# irDA.net
KiCad netlist of a schematic drawn in EAGLE
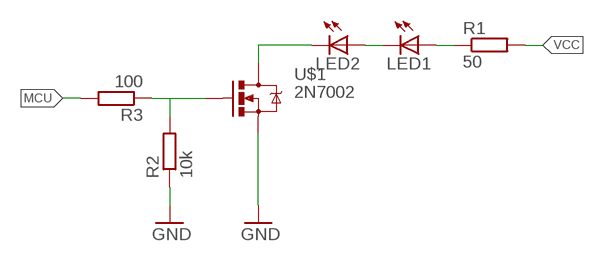
[diagram p0: schematic, sheet 1]

(export (version "E")
  (design (tool "Eeschema 10.0.6"))
  (components
    (comp (ref "LED1")
      (value "LED5MM")
      (footprint "eagle-import:LED5MM")
      (libsource (lib "eagle-import") (part "LED5MM"))
    )
    (comp (ref "LED2")
      (value "LED5MM")
      (footprint "eagle-import:LED5MM")
      (libsource (lib "eagle-import") (part "LED5MM"))
    )
    (comp (ref "R1")
      (value "50")
      (footprint "eagle-import:R0805")
      (libsource (lib "eagle-import") (part "R0805"))
    )
    (comp (ref "R2")
      (value "10k")
      (footprint "eagle-import:0603")
      (libsource (lib "eagle-import") (part "R0603"))
    )
    (comp (ref "R3")
      (value "100")
      (footprint "eagle-import:0603")
      (libsource (lib "eagle-import") (part "R0603"))
    )
    (comp (ref "U$1")
      (value "2N7002")
      (footprint "eagle-import:SOT23")
      (libsource (lib "eagle-import") (part "2N7002"))
    )
  )
  (nets
    (net (code "1") (name "GND") (class "Default")
      (node (ref "R2") (pin "1") (pinfunction "1_1") (pintype "passive"))
      (node (ref "U$1") (pin "2") (pinfunction "S_2") (pintype "passive"))
    )
    (net (code "2") (name "MCU") (class "Default")
      (node (ref "R3") (pin "2") (pinfunction "2_2") (pintype "passive"))
    )
    (net (code "3") (name "Net-(LED1-C)") (class "Default")
      (node (ref "LED1") (pin "K") (pinfunction "C_K") (pintype "passive"))
      (node (ref "LED2") (pin "A") (pinfunction "A_A") (pintype "passive"))
    )
    (net (code "4") (name "Net-(LED1-PadA)") (class "Default")
      (node (ref "LED1") (pin "A") (pinfunction "A_A") (pintype "passive"))
      (node (ref "R1") (pin "1") (pinfunction "1_1") (pintype "passive"))
    )
    (net (code "5") (name "Net-(LED2-C)") (class "Default")
      (node (ref "LED2") (pin "K") (pinfunction "C_K") (pintype "passive"))
      (node (ref "U$1") (pin "3") (pinfunction "D_3") (pintype "passive"))
    )
    (net (code "6") (name "Net-(U$1-G)") (class "Default")
      (node (ref "R2") (pin "2") (pinfunction "2_2") (pintype "passive"))
      (node (ref "R3") (pin "1") (pinfunction "1_1") (pintype "passive"))
      (node (ref "U$1") (pin "1") (pinfunction "G_1") (pintype "passive"))
    )
    (net (code "7") (name "VCC") (class "Default")
      (node (ref "R1") (pin "2") (pinfunction "2_2") (pintype "passive"))
    )
  )
)
